# Tally_Box.net
KiCad netlist of a schematic drawn in EAGLE
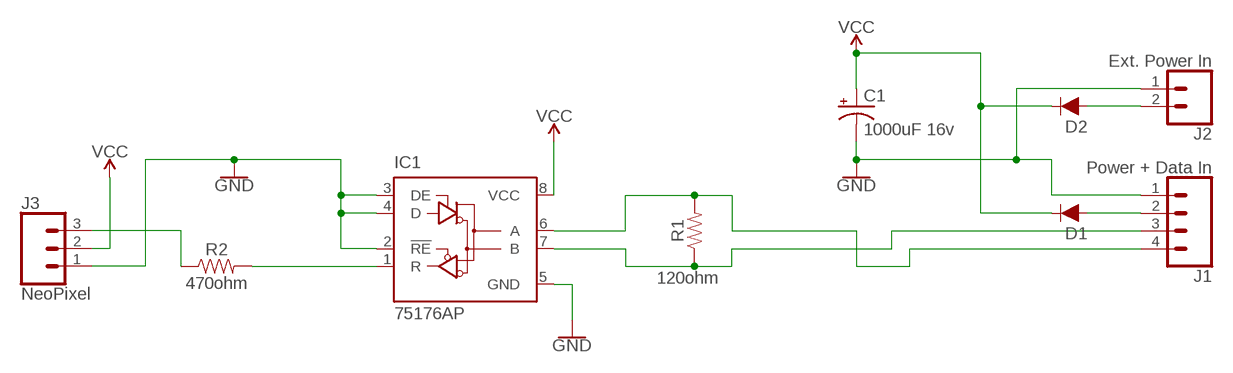
[diagram p0: schematic, sheet 1]

(export (version "E")
  (design (tool "Eeschema 10.0.6"))
  (components
    (comp (ref "C1")
      (value "1000uF 16v")
      (footprint "eagle-import:CPOL-RADIAL-5MM-10MM")
      (libsource (lib "eagle-import") (part "1000UF-RADIAL-5MM-25V-20%"))
    )
    (comp (ref "D1")
      (value "DIODE-PTH")
      (footprint "eagle-import:DIODE-1N4001")
      (libsource (lib "eagle-import") (part "DIODE-PTH"))
    )
    (comp (ref "D2")
      (value "DIODE-PTH")
      (footprint "eagle-import:DIODE-1N4001")
      (libsource (lib "eagle-import") (part "DIODE-PTH"))
    )
    (comp (ref "IC1")
      (value "75176AP")
      (footprint "eagle-import:DIL08")
      (libsource (lib "eagle-import") (part "75176AP"))
    )
    (comp (ref "J1")
      (value "Power + Data In")
      (footprint "eagle-import:1X04")
      (libsource (lib "eagle-import") (part "CONN_04PTH"))
    )
    (comp (ref "J2")
      (value "Ext. Power In")
      (footprint "eagle-import:1X02")
      (libsource (lib "eagle-import") (part "CONN_02"))
    )
    (comp (ref "J3")
      (value "NeoPixel")
      (footprint "eagle-import:1X03")
      (libsource (lib "eagle-import") (part "CONN_03"))
    )
    (comp (ref "R1")
      (value "120ohm")
      (footprint "eagle-import:AXIAL-0.3")
      (libsource (lib "eagle-import") (part "RESISTORAXIAL-0.3"))
    )
    (comp (ref "R2")
      (value "470ohm")
      (footprint "eagle-import:AXIAL-0.3")
      (libsource (lib "eagle-import") (part "RESISTORAXIAL-0.3"))
    )
  )
  (nets
    (net (code "1") (name "GND") (class "Default")
      (node (ref "C1") (pin "-") (pinfunction "-_-") (pintype "passive"))
      (node (ref "IC1") (pin "2") (pinfunction "~{RE}_2") (pintype "input"))
      (node (ref "IC1") (pin "3") (pinfunction "DE_3") (pintype "input"))
      (node (ref "IC1") (pin "4") (pinfunction "D_4") (pintype "input"))
      (node (ref "IC1") (pin "5") (pinfunction "GND_5") (pintype "power_in"))
      (node (ref "J1") (pin "1") (pinfunction "1_1") (pintype "passive"))
      (node (ref "J2") (pin "1") (pinfunction "1_1") (pintype "passive"))
      (node (ref "J3") (pin "1") (pinfunction "1_1") (pintype "passive"))
    )
    (net (code "2") (name "Net-(D1-PadA)") (class "Default")
      (node (ref "D1") (pin "A") (pinfunction "A_A") (pintype "passive"))
      (node (ref "J1") (pin "2") (pinfunction "2_2") (pintype "passive"))
    )
    (net (code "3") (name "Net-(D2-PadA)") (class "Default")
      (node (ref "D2") (pin "A") (pinfunction "A_A") (pintype "passive"))
      (node (ref "J2") (pin "2") (pinfunction "2_2") (pintype "passive"))
    )
    (net (code "4") (name "Net-(IC1-A)") (class "Default")
      (node (ref "IC1") (pin "6") (pinfunction "A_6") (pintype "output"))
      (node (ref "J1") (pin "4") (pinfunction "4_4") (pintype "passive"))
      (node (ref "R1") (pin "P$2") (pinfunction "2_P$2") (pintype "passive"))
    )
    (net (code "5") (name "Net-(IC1-B)") (class "Default")
      (node (ref "IC1") (pin "7") (pinfunction "B_7") (pintype "output"))
      (node (ref "J1") (pin "3") (pinfunction "3_3") (pintype "passive"))
      (node (ref "R1") (pin "P$1") (pinfunction "1_P$1") (pintype "passive"))
    )
    (net (code "6") (name "Net-(IC1-R)") (class "Default")
      (node (ref "IC1") (pin "1") (pinfunction "R_1") (pintype "input"))
      (node (ref "R2") (pin "P$2") (pinfunction "2_P$2") (pintype "passive"))
    )
    (net (code "7") (name "Net-(R2-1)") (class "Default")
      (node (ref "J3") (pin "3") (pinfunction "3_3") (pintype "passive"))
      (node (ref "R2") (pin "P$1") (pinfunction "1_P$1") (pintype "passive"))
    )
    (net (code "8") (name "VCC") (class "Default")
      (node (ref "C1") (pin "+") (pinfunction "+_+") (pintype "passive"))
      (node (ref "D1") (pin "C") (pinfunction "C_C") (pintype "passive"))
      (node (ref "D2") (pin "C") (pinfunction "C_C") (pintype "passive"))
      (node (ref "IC1") (pin "8") (pinfunction "VCC_8") (pintype "power_in"))
      (node (ref "J3") (pin "2") (pinfunction "2_2") (pintype "passive"))
    )
  )
)
